# sch_pwr_brd_sensors.net
KiCad netlist of a schematic drawn in Altium Designer
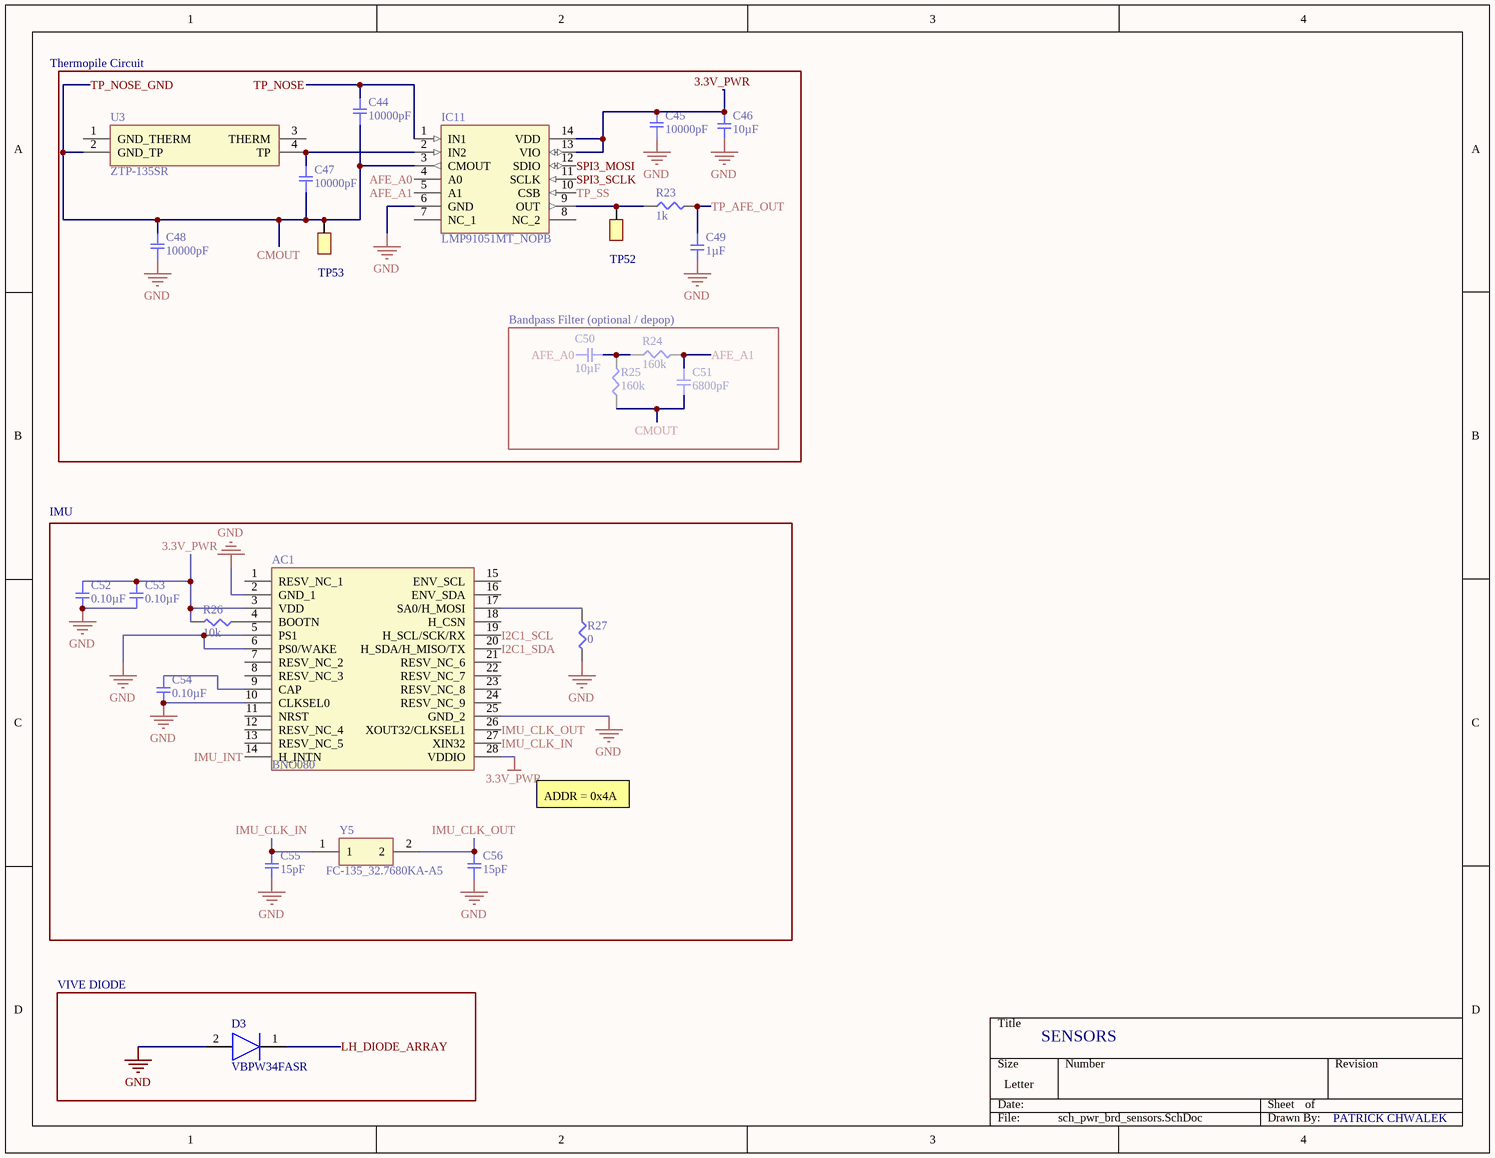
[diagram p0: sch_pwr_brd_sensors.SchDoc]

(export (version "E")
  (design (tool "Eeschema 10.0.6"))
  (components
    (comp (ref "AC1")
      (value "BNO080")
      (footprint "SamacSys:BNO080")
      (description "Accelerometer")
      (libsource (lib "*") (part "BNO080"))
    )
    (comp (ref "C44")
      (value "10000pF")
      (footprint "SMD-0402C")
      (description "CAP CER 10000PF 50V X7R 0402")
      (fields
        (field (name "DIGI-KEY PART NUMBER") "490-4762-1-ND")
        (field (name "PART NUMBER") "GCM155R71H103KA55D")
      )
      (libsource (lib "capacitor_murata_0402") (part "GCM155R71H103KA55D"))
    )
    (comp (ref "C45")
      (value "10000pF")
      (footprint "SMD-0402C")
      (description "CAP CER 10000PF 50V X7R 0402")
      (fields
        (field (name "DIGI-KEY PART NUMBER") "490-4762-1-ND")
        (field (name "PART NUMBER") "GCM155R71H103KA55D")
      )
      (libsource (lib "capacitor_murata_0402") (part "GCM155R71H103KA55D"))
    )
    (comp (ref "C46")
      (value "10µF")
      (footprint "SMD-0402C")
      (description "CAP CER 10UF 6.3V X5R 0402")
      (fields
        (field (name "DIGI-KEY PART NUMBER") "490-13211-1-ND")
        (field (name "PART NUMBER") "GRJ155R60J106ME11D")
      )
      (libsource (lib "capacitor_murata_0402") (part "GRJ155R60J106ME11D"))
    )
    (comp (ref "C47")
      (value "10000pF")
      (footprint "SMD-0402C")
      (description "CAP CER 10000PF 50V X7R 0402")
      (fields
        (field (name "DIGI-KEY PART NUMBER") "490-4762-1-ND")
        (field (name "PART NUMBER") "GCM155R71H103KA55D")
      )
      (libsource (lib "capacitor_murata_0402") (part "GCM155R71H103KA55D"))
    )
    (comp (ref "C48")
      (value "10000pF")
      (footprint "SMD-0402C")
      (description "CAP CER 10000PF 50V X7R 0402")
      (fields
        (field (name "DIGI-KEY PART NUMBER") "490-4762-1-ND")
        (field (name "PART NUMBER") "GCM155R71H103KA55D")
      )
      (libsource (lib "capacitor_murata_0402") (part "GCM155R71H103KA55D"))
    )
    (comp (ref "C49")
      (value "1µF")
      (footprint "SMD-0402C")
      (description "CAP CER 1UF 10V X7S 0402")
      (fields
        (field (name "DIGI-KEY PART NUMBER") "490-13409-1-ND")
        (field (name "PART NUMBER") "GCM155C71A105KE38D")
      )
      (libsource (lib "capacitor_murata_0402") (part "GCM155C71A105KE38D"))
    )
    (comp (ref "C50")
      (value "10µF")
      (footprint "SMD-0402C")
      (description "CAP CER 10UF 6.3V X5R 0402")
      (fields
        (field (name "DIGI-KEY PART NUMBER") "490-13211-1-ND")
        (field (name "PART NUMBER") "GRJ155R60J106ME11D")
      )
      (libsource (lib "capacitor_murata_0402") (part "GRJ155R60J106ME11D"))
    )
    (comp (ref "C51")
      (value "6800pF")
      (footprint "SMD-0402C")
      (description "CAP CER 6800PF 25V X7R 0402")
      (fields
        (field (name "DIGI-KEY PART NUMBER") "490-11422-1-ND")
        (field (name "PART NUMBER") "GRM155R71E682KA01J")
      )
      (libsource (lib "capacitor_murata_0402") (part "GRM155R71E682KA01J"))
    )
    (comp (ref "C52")
      (value "0.10µF")
      (footprint "CAPC1005X55N")
      (description "CAP CER 0.1UF 16V X7R 0402")
      (fields
        (field (name "DIGI-KEY PART NUMBER") "490-4759-1-ND")
        (field (name "PART NUMBER") "GCM155R71C104KA55D")
      )
      (libsource (lib "capacitor_murata_0402") (part "GCM155R71C104KA55D"))
    )
    (comp (ref "C53")
      (value "0.10µF")
      (footprint "CAPC1005X55N")
      (description "CAP CER 0.1UF 16V X7R 0402")
      (fields
        (field (name "DIGI-KEY PART NUMBER") "490-4759-1-ND")
        (field (name "PART NUMBER") "GCM155R71C104KA55D")
      )
      (libsource (lib "capacitor_murata_0402") (part "GCM155R71C104KA55D"))
    )
    (comp (ref "C54")
      (value "0.10µF")
      (footprint "CAPC1005X55N")
      (description "CAP CER 0.1UF 16V X7R 0402")
      (fields
        (field (name "DIGI-KEY PART NUMBER") "490-4759-1-ND")
        (field (name "PART NUMBER") "GCM155R71C104KA55D")
      )
      (libsource (lib "capacitor_murata_0402") (part "GCM155R71C104KA55D"))
    )
    (comp (ref "C55")
      (value "15pF")
      (footprint "CAPC1005X55N")
      (description "CAP CER 15PF 50V NP0 0402")
      (fields
        (field (name "DIGI-KEY PART NUMBER") "490-11147-1-ND")
        (field (name "PART NUMBER") "GCM1555C1H150JA16D")
      )
      (libsource (lib "capacitor_murata_0402") (part "GCM1555C1H150JA16D"))
    )
    (comp (ref "C56")
      (value "15pF")
      (footprint "CAPC1005X55N")
      (description "CAP CER 15PF 50V NP0 0402")
      (fields
        (field (name "DIGI-KEY PART NUMBER") "490-11147-1-ND")
        (field (name "PART NUMBER") "GCM1555C1H150JA16D")
      )
      (libsource (lib "capacitor_murata_0402") (part "GCM1555C1H150JA16D"))
    )
    (comp (ref "D3")
      (value "VBPW34FASR")
      (footprint "VBPW34FASR")
      (description "Diode")
      (fields (field (name "MOUSER PART NUMBER") "782-VBPW34FASR") (field (name "RS PART NUMBER") "7689401"))
      (libsource (lib "*") (part "VBPW34FASR"))
    )
    (comp (ref "IC11")
      (value "LMP91051MT_NOPB")
      (footprint "SOP65P640X120-14N")
      (description "Integrated Circuit")
      (fields
        (field (name "MANUFACTURER_PART_NUMBER") "LMP91051MT/NOPB")
        (field (name "MOUSER PART NUMBER") "595-LMP91051MT/NOPB")
      )
      (libsource (lib "*") (part "LMP91051MT_NOPB"))
    )
    (comp (ref "R23")
      (value "1k")
      (footprint "SMD-0402-RES")
      (description "RES SMD 1K OHM 5% 1/10W 0402")
      (fields (field (name "PART NUMBER") "ERJ-2GEJ102X") (field (name "DIGI-KEY PART NUMBER") "P1.0KJCT-ND"))
      (libsource (lib "Panasonic_ERJ_0402") (part "ERJ-2GEJ102X"))
    )
    (comp (ref "R24")
      (value "160k")
      (footprint "SMD-0402-RES")
      (description "RES SMD 160K OHM 5% 1/10W 0402")
      (fields (field (name "PART NUMBER") "ERJ-2GEJ164X") (field (name "DIGI-KEY PART NUMBER") "P160KJCT-ND"))
      (libsource (lib "Panasonic_ERJ_0402") (part "ERJ-2GEJ164X"))
    )
    (comp (ref "R25")
      (value "160k")
      (footprint "SMD-0402-RES")
      (description "RES SMD 160K OHM 5% 1/10W 0402")
      (fields (field (name "PART NUMBER") "ERJ-2GEJ164X") (field (name "DIGI-KEY PART NUMBER") "P160KJCT-ND"))
      (libsource (lib "Panasonic_ERJ_0402") (part "ERJ-2GEJ164X"))
    )
    (comp (ref "R26")
      (value "10k")
      (footprint "SMD-0402-RES")
      (description "RES SMD 10K OHM 5% 1/10W 0402")
      (fields (field (name "PART NUMBER") "ERJ-2GEJ103X") (field (name "DIGI-KEY PART NUMBER") "P10KJCT-ND"))
      (libsource (lib "Panasonic_ERJ_0402") (part "ERJ-2GEJ103X"))
    )
    (comp (ref "R27")
      (value "0")
      (footprint "SMD-0402-RES")
      (description "RES SMD 0K OHM 5% 1/10W 0402")
      (fields (field (name "PART NUMBER") "ERJ-2GEJ103X") (field (name "DIGI-KEY PART NUMBER") "P10KJCT-ND"))
      (libsource (lib "Panasonic_ERJ_0402") (part "ERJ-2GEJ103X"))
    )
    (comp (ref "TP52")
      (value "TestPoint")
      (footprint "TestPoint_0.4mm")
      (libsource (lib "schematic_components") (part "TestPoint"))
    )
    (comp (ref "TP53")
      (value "TestPoint")
      (footprint "TestPoint_0.4mm")
      (libsource (lib "schematic_components") (part "TestPoint"))
    )
    (comp (ref "U3")
      (value "ZTP-135SR")
      (footprint "ZTP-135SR")
      (description "Undefined or Miscellaneous")
      (fields (field (name "MOUSER PART NUMBER") "527-ZTP-135SR"))
      (libsource (lib "SamacSys") (part "ZTP-135SR"))
    )
    (comp (ref "Y5")
      (value "FC-135_32.7680KA-A5")
      (footprint "SamacSys:FC135327680KAAG0")
      (description "Crystal or Oscillator")
      (fields
        (field (name "MANUFACTURER_PART_NUMBER") "FC-135 32.7680KA-A5")
        (field (name "MOUSER PART NUMBER") "732-FC135-32.76KAA3")
      )
      (libsource (lib "*") (part "FC-135_32.7680KA-A3"))
    )
  )
  (nets
    (net (code "1") (name "/AFE_A0") (class "Default")
      (node (ref "C50") (pin "1") (pinfunction "1_1") (pintype "passive"))
      (node (ref "IC11") (pin "4") (pinfunction "A0_4") (pintype "passive"))
    )
    (net (code "2") (name "/AFE_A1") (class "Default")
      (node (ref "C51") (pin "1") (pinfunction "1_1") (pintype "passive"))
      (node (ref "IC11") (pin "5") (pinfunction "A1_5") (pintype "passive"))
      (node (ref "R24") (pin "2") (pinfunction "2_2") (pintype "passive"))
    )
    (net (code "3") (name "/CMOUT") (class "Default")
      (node (ref "C44") (pin "1") (pinfunction "1_1") (pintype "passive"))
      (node (ref "C47") (pin "1") (pinfunction "1_1") (pintype "passive"))
      (node (ref "C48") (pin "2") (pinfunction "2_2") (pintype "passive"))
      (node (ref "C51") (pin "2") (pinfunction "2_2") (pintype "passive"))
      (node (ref "IC11") (pin "3") (pinfunction "CMOUT_3") (pintype "output"))
      (node (ref "R25") (pin "1") (pinfunction "1_1") (pintype "passive"))
      (node (ref "TP53") (pin "1") (pinfunction "1_1") (pintype "passive"))
      (node (ref "U3") (pin "2") (pinfunction "GND_TP_2") (pintype "passive"))
    )
    (net (code "4") (name "/I2C1_SCL") (class "Default")
      (node (ref "AC1") (pin "19") (pinfunction "H_SCL/SCK/RX_19") (pintype "passive"))
    )
    (net (code "5") (name "/I2C1_SDA") (class "Default")
      (node (ref "AC1") (pin "20") (pinfunction "H_SDA/H_MISO/TX_20") (pintype "passive"))
    )
    (net (code "6") (name "/IMU_CLK_IN") (class "Default")
      (node (ref "AC1") (pin "27") (pinfunction "XIN32_27") (pintype "passive"))
      (node (ref "C55") (pin "1") (pinfunction "1_1") (pintype "passive"))
      (node (ref "Y5") (pin "1") (pinfunction "1_1") (pintype "passive"))
    )
    (net (code "7") (name "/IMU_CLK_OUT") (class "Default")
      (node (ref "AC1") (pin "26") (pinfunction "XOUT32/CLKSEL1_26") (pintype "passive"))
      (node (ref "C56") (pin "1") (pinfunction "1_1") (pintype "passive"))
      (node (ref "Y5") (pin "2") (pinfunction "2_2") (pintype "passive"))
    )
    (net (code "8") (name "/IMU_INT") (class "Default")
      (node (ref "AC1") (pin "14") (pinfunction "H_INTN_14") (pintype "passive"))
    )
    (net (code "9") (name "/LH_DIODE_ARRAY") (class "Default")
      (node (ref "D3") (pin "1") (pinfunction "A_1") (pintype "passive"))
    )
    (net (code "10") (name "/SPI3_MOSI") (class "Default")
      (node (ref "IC11") (pin "12") (pinfunction "SDIO_12") (pintype "bidirectional"))
    )
    (net (code "11") (name "/SPI3_SCLK") (class "Default")
      (node (ref "IC11") (pin "11") (pinfunction "SCLK_11") (pintype "input"))
    )
    (net (code "12") (name "/TP_AFE_OUT") (class "Default")
      (node (ref "C49") (pin "1") (pinfunction "1_1") (pintype "passive"))
      (node (ref "R23") (pin "2") (pinfunction "2_2") (pintype "passive"))
    )
    (net (code "13") (name "/TP_NOSE") (class "Default")
      (node (ref "C44") (pin "2") (pinfunction "2_2") (pintype "passive"))
      (node (ref "IC11") (pin "1") (pinfunction "IN1_1") (pintype "input"))
    )
    (net (code "14") (name "/TP_SS") (class "Default")
      (node (ref "IC11") (pin "10") (pinfunction "CSB_10") (pintype "input"))
    )
    (net (code "15") (name "3.3V_PWR") (class "Default")
      (node (ref "AC1") (pin "28") (pinfunction "VDDIO_28") (pintype "passive"))
      (node (ref "AC1") (pin "3") (pinfunction "VDD_3") (pintype "passive"))
      (node (ref "C45") (pin "2") (pinfunction "2_2") (pintype "passive"))
      (node (ref "C46") (pin "1") (pinfunction "1_1") (pintype "passive"))
      (node (ref "C52") (pin "1") (pinfunction "1_1") (pintype "passive"))
      (node (ref "C53") (pin "1") (pinfunction "1_1") (pintype "passive"))
      (node (ref "IC11") (pin "13") (pinfunction "VIO_13") (pintype "bidirectional"))
      (node (ref "IC11") (pin "14") (pinfunction "VDD_14") (pintype "power_in"))
      (node (ref "R26") (pin "2") (pinfunction "2_2") (pintype "passive"))
    )
    (net (code "16") (name "GND") (class "Default")
      (node (ref "AC1") (pin "10") (pinfunction "CLKSEL0_10") (pintype "passive"))
      (node (ref "AC1") (pin "2") (pinfunction "GND_1_2") (pintype "passive"))
      (node (ref "AC1") (pin "25") (pinfunction "GND_2_25") (pintype "passive"))
      (node (ref "AC1") (pin "5") (pinfunction "PS1_5") (pintype "passive"))
      (node (ref "AC1") (pin "6") (pinfunction "PS0/WAKE_6") (pintype "passive"))
      (node (ref "C45") (pin "1") (pinfunction "1_1") (pintype "passive"))
      (node (ref "C46") (pin "2") (pinfunction "2_2") (pintype "passive"))
      (node (ref "C48") (pin "1") (pinfunction "1_1") (pintype "passive"))
      (node (ref "C49") (pin "2") (pinfunction "2_2") (pintype "passive"))
      (node (ref "C52") (pin "2") (pinfunction "2_2") (pintype "passive"))
      (node (ref "C53") (pin "2") (pinfunction "2_2") (pintype "passive"))
      (node (ref "C54") (pin "2") (pinfunction "2_2") (pintype "passive"))
      (node (ref "C55") (pin "2") (pinfunction "2_2") (pintype "passive"))
      (node (ref "C56") (pin "2") (pinfunction "2_2") (pintype "passive"))
      (node (ref "D3") (pin "2") (pinfunction "K_2") (pintype "passive"))
      (node (ref "IC11") (pin "6") (pinfunction "GND_6") (pintype "power_in"))
      (node (ref "R27") (pin "2") (pinfunction "2_2") (pintype "passive"))
    )
    (net (code "17") (name "Net-(AC1-BOOTN)") (class "Default")
      (node (ref "AC1") (pin "4") (pinfunction "BOOTN_4") (pintype "passive"))
      (node (ref "R26") (pin "1") (pinfunction "1_1") (pintype "passive"))
    )
    (net (code "18") (name "Net-(AC1-CAP)") (class "Default")
      (node (ref "AC1") (pin "9") (pinfunction "CAP_9") (pintype "passive"))
      (node (ref "C54") (pin "1") (pinfunction "1_1") (pintype "passive"))
    )
    (net (code "19") (name "Net-(AC1-SA0{slash}H_MOSI)") (class "Default")
      (node (ref "AC1") (pin "17") (pinfunction "SA0/H_MOSI_17") (pintype "passive"))
      (node (ref "R27") (pin "1") (pinfunction "1_1") (pintype "passive"))
    )
    (net (code "20") (name "Net-(C50-Pad2)") (class "Default")
      (node (ref "C50") (pin "2") (pinfunction "2_2") (pintype "passive"))
      (node (ref "R24") (pin "1") (pinfunction "1_1") (pintype "passive"))
      (node (ref "R25") (pin "2") (pinfunction "2_2") (pintype "passive"))
    )
    (net (code "21") (name "Net-(IC11-IN2)") (class "Default")
      (node (ref "C47") (pin "2") (pinfunction "2_2") (pintype "passive"))
      (node (ref "IC11") (pin "2") (pinfunction "IN2_2") (pintype "input"))
      (node (ref "U3") (pin "4") (pinfunction "TP_4") (pintype "passive"))
    )
    (net (code "22") (name "Net-(IC11-OUT)") (class "Default")
      (node (ref "IC11") (pin "9") (pinfunction "OUT_9") (pintype "output"))
      (node (ref "R23") (pin "1") (pinfunction "1_1") (pintype "passive"))
      (node (ref "TP52") (pin "1") (pinfunction "1_1") (pintype "passive"))
    )
    (net (code "23") (name "unconnected-(AC1-ENV_SCL-Pad15)") (class "Default")
      (node (ref "AC1") (pin "15") (pinfunction "ENV_SCL_15") (pintype "passive"))
    )
    (net (code "24") (name "unconnected-(AC1-ENV_SDA-Pad16)") (class "Default")
      (node (ref "AC1") (pin "16") (pinfunction "ENV_SDA_16") (pintype "passive"))
    )
    (net (code "25") (name "unconnected-(AC1-H_CSN-Pad18)") (class "Default")
      (node (ref "AC1") (pin "18") (pinfunction "H_CSN_18") (pintype "passive"))
    )
    (net (code "26") (name "unconnected-(AC1-NRST-Pad11)") (class "Default")
      (node (ref "AC1") (pin "11") (pinfunction "NRST_11") (pintype "passive"))
    )
    (net (code "27") (name "unconnected-(AC1-RESV_NC_1-Pad1)") (class "Default")
      (node (ref "AC1") (pin "1") (pinfunction "RESV_NC_1_1") (pintype "passive"))
    )
    (net (code "28") (name "unconnected-(AC1-RESV_NC_2-Pad7)") (class "Default")
      (node (ref "AC1") (pin "7") (pinfunction "RESV_NC_2_7") (pintype "passive"))
    )
    (net (code "29") (name "unconnected-(AC1-RESV_NC_3-Pad8)") (class "Default")
      (node (ref "AC1") (pin "8") (pinfunction "RESV_NC_3_8") (pintype "passive"))
    )
    (net (code "30") (name "unconnected-(AC1-RESV_NC_4-Pad12)") (class "Default")
      (node (ref "AC1") (pin "12") (pinfunction "RESV_NC_4_12") (pintype "passive"))
    )
    (net (code "31") (name "unconnected-(AC1-RESV_NC_5-Pad13)") (class "Default")
      (node (ref "AC1") (pin "13") (pinfunction "RESV_NC_5_13") (pintype "passive"))
    )
    (net (code "32") (name "unconnected-(AC1-RESV_NC_6-Pad21)") (class "Default")
      (node (ref "AC1") (pin "21") (pinfunction "RESV_NC_6_21") (pintype "passive"))
    )
    (net (code "33") (name "unconnected-(AC1-RESV_NC_7-Pad22)") (class "Default")
      (node (ref "AC1") (pin "22") (pinfunction "RESV_NC_7_22") (pintype "passive"))
    )
    (net (code "34") (name "unconnected-(AC1-RESV_NC_8-Pad23)") (class "Default")
      (node (ref "AC1") (pin "23") (pinfunction "RESV_NC_8_23") (pintype "passive"))
    )
    (net (code "35") (name "unconnected-(AC1-RESV_NC_9-Pad24)") (class "Default")
      (node (ref "AC1") (pin "24") (pinfunction "RESV_NC_9_24") (pintype "passive"))
    )
    (net (code "36") (name "unconnected-(IC11-NC_1-Pad7)") (class "Default")
      (node (ref "IC11") (pin "7") (pinfunction "NC_1_7") (pintype "passive"))
    )
    (net (code "37") (name "unconnected-(IC11-NC_2-Pad8)") (class "Default")
      (node (ref "IC11") (pin "8") (pinfunction "NC_2_8") (pintype "passive"))
    )
    (net (code "38") (name "unconnected-(U3-GND_THERM-Pad1)") (class "Default")
      (node (ref "U3") (pin "1") (pinfunction "GND_THERM_1") (pintype "passive"))
    )
    (net (code "39") (name "unconnected-(U3-THERM-Pad3)") (class "Default")
      (node (ref "U3") (pin "3") (pinfunction "THERM_3") (pintype "passive"))
    )
  )
)
